# Sheet_1_2022-03-27.net
KiCad netlist of a schematic drawn in Altium Designer
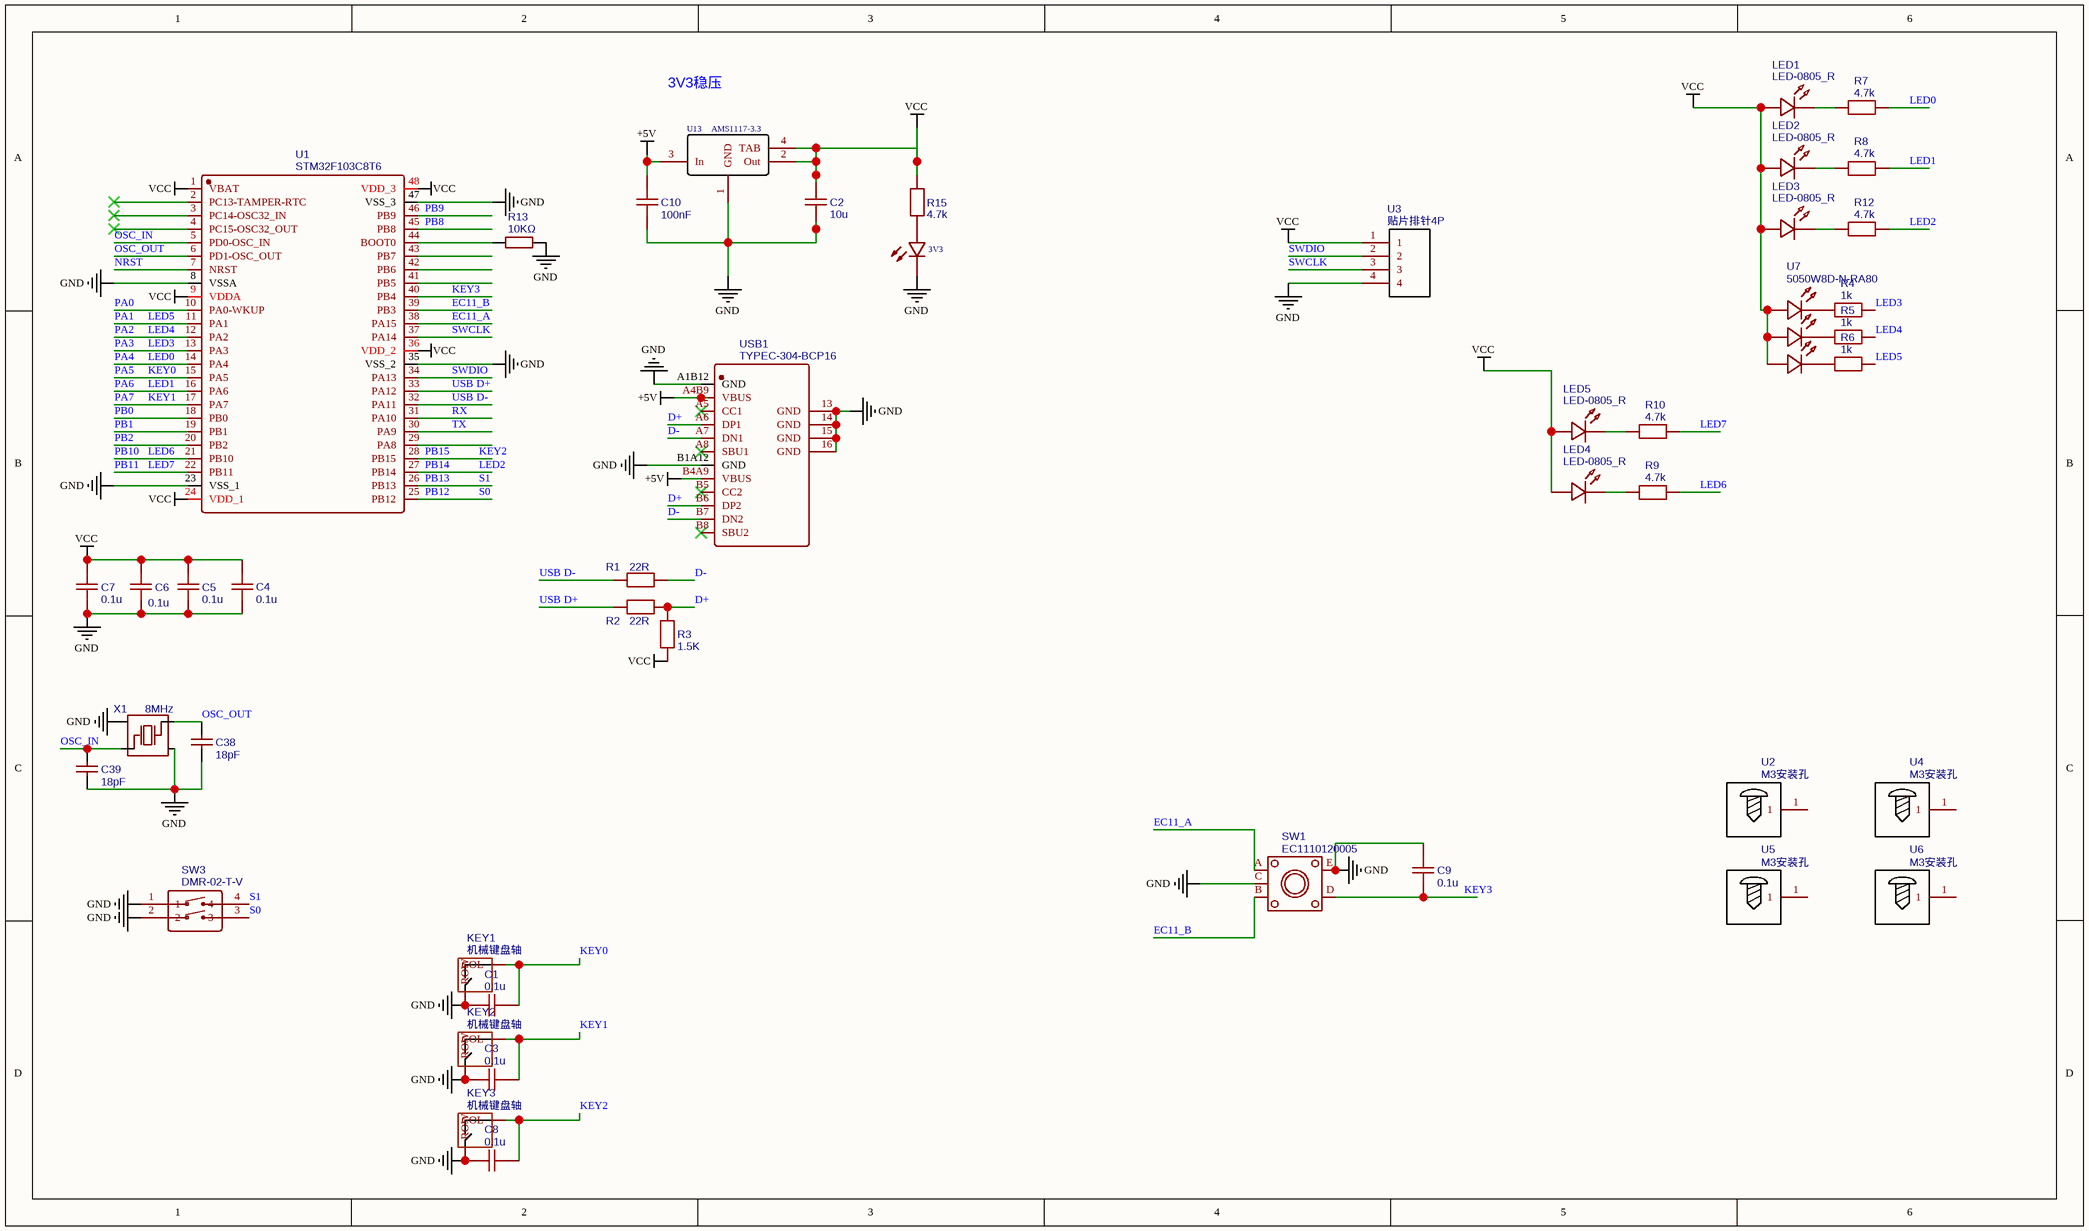
[diagram p0: Sheet_1_2022-03-27.schdoc]

(export (version "E")
  (design (tool "Eeschema 10.0.6"))
  (components
    (comp (ref "3V3")
      (value "17-21/BHC-XL2M2TY/3T")
      (fields (field (name "BOM_SUPPLIER PART") "C72035"))
      (libsource (lib "altium-import") (part "root_1_17-21/BHC-XL2M2TY/3T_"))
    )
    (comp (ref "C1")
      (value "0.1u")
      (fields (field (name "CONTRIBUTOR") "LCEDA_Lib"))
      (libsource (lib "altium-import") (part "root_2_0.1u_"))
    )
    (comp (ref "C2")
      (value "10u")
      (fields (field (name "CONTRIBUTOR") "LCEDA_Lib"))
      (libsource (lib "altium-import") (part "root_1_10u_"))
    )
    (comp (ref "C3")
      (value "0.1u")
      (fields (field (name "CONTRIBUTOR") "LCEDA_Lib"))
      (libsource (lib "altium-import") (part "root_0_0.1u_"))
    )
    (comp (ref "C4")
      (value "0.1u")
      (fields (field (name "CONTRIBUTOR") "LCEDA_Lib"))
      (libsource (lib "altium-import") (part "root_1_0.1u_"))
    )
    (comp (ref "C5")
      (value "0.1u")
      (fields (field (name "CONTRIBUTOR") "LCEDA_Lib"))
      (libsource (lib "altium-import") (part "root_1_0.1u_"))
    )
    (comp (ref "C6")
      (value "0.1u")
      (fields (field (name "CONTRIBUTOR") "LCEDA_Lib"))
      (libsource (lib "altium-import") (part "root_1_0.1u_"))
    )
    (comp (ref "C7")
      (value "0.1u")
      (fields (field (name "CONTRIBUTOR") "LCEDA_Lib"))
      (libsource (lib "altium-import") (part "root_1_0.1u_"))
    )
    (comp (ref "C8")
      (value "0.1u")
      (fields (field (name "CONTRIBUTOR") "LCEDA_Lib"))
      (libsource (lib "altium-import") (part "root_0_0.1u_"))
    )
    (comp (ref "C9")
      (value "0.1u")
      (fields (field (name "CONTRIBUTOR") "LCEDA_Lib"))
      (libsource (lib "altium-import") (part "root_3_0.1u_"))
    )
    (comp (ref "C10")
      (value "100nF")
      (fields (field (name "CONTRIBUTOR") "LCEDA_Lib"))
      (libsource (lib "altium-import") (part "root_1_100nF_"))
    )
    (comp (ref "C38")
      (value "18pF")
      (fields
        (field (name "BOM_MANUFACTURER PART") "CL10C180JB8NNNC")
        (field (name "BOM_SUPPLIER PART") "C1647")
      )
      (libsource (lib "altium-import") (part "root_1_18pF_"))
    )
    (comp (ref "C39")
      (value "18pF")
      (fields
        (field (name "BOM_MANUFACTURER PART") "CL10C180JB8NNNC")
        (field (name "BOM_SUPPLIER PART") "C1647")
      )
      (libsource (lib "altium-import") (part "root_1_18pF_"))
    )
    (comp (ref "KEY1")
      (value "机械键盘轴")
      (fields (field (name "CONTRIBUTOR") "Ptisak"))
      (libsource (lib "altium-import") (part "root_2_机械键盘轴_"))
    )
    (comp (ref "KEY2")
      (value "机械键盘轴")
      (fields (field (name "CONTRIBUTOR") "Ptisak"))
      (libsource (lib "altium-import") (part "root_2_机械键盘轴_"))
    )
    (comp (ref "KEY3")
      (value "机械键盘轴")
      (fields (field (name "CONTRIBUTOR") "Ptisak"))
      (libsource (lib "altium-import") (part "root_2_机械键盘轴_"))
    )
    (comp (ref "LED1")
      (value "LED-0805_R")
      (fields
        (field (name "BOM_MANUFACTURER PART") "17-21SURC/S530-A3/TR8")
        (field (name "BOM_SUPPLIER PART") "C72037")
        (field (name "CONTRIBUTOR") "LCEDA_Lib")
      )
      (libsource (lib "altium-import") (part "root_0_LED-0805_R_"))
    )
    (comp (ref "LED2")
      (value "LED-0805_R")
      (fields
        (field (name "BOM_MANUFACTURER PART") "17-21SURC/S530-A3/TR8")
        (field (name "BOM_SUPPLIER PART") "C72037")
        (field (name "CONTRIBUTOR") "LCEDA_Lib")
      )
      (libsource (lib "altium-import") (part "root_0_LED-0805_R_"))
    )
    (comp (ref "LED3")
      (value "LED-0805_R")
      (fields
        (field (name "BOM_MANUFACTURER PART") "17-21SURC/S530-A3/TR8")
        (field (name "BOM_SUPPLIER PART") "C72037")
        (field (name "CONTRIBUTOR") "LCEDA_Lib")
      )
      (libsource (lib "altium-import") (part "root_0_LED-0805_R_"))
    )
    (comp (ref "LED4")
      (value "LED-0805_R")
      (fields
        (field (name "BOM_MANUFACTURER PART") "17-21SURC/S530-A3/TR8")
        (field (name "BOM_SUPPLIER PART") "C72037")
        (field (name "CONTRIBUTOR") "LCEDA_Lib")
      )
      (libsource (lib "altium-import") (part "root_0_LED-0805_R_"))
    )
    (comp (ref "LED5")
      (value "LED-0805_R")
      (fields
        (field (name "BOM_MANUFACTURER PART") "17-21SURC/S530-A3/TR8")
        (field (name "BOM_SUPPLIER PART") "C72037")
        (field (name "CONTRIBUTOR") "LCEDA_Lib")
      )
      (libsource (lib "altium-import") (part "root_0_LED-0805_R_"))
    )
    (comp (ref "R1")
      (value "22R")
      (fields (field (name "CONTRIBUTOR") "LCEDA_Lib"))
      (libsource (lib "altium-import") (part "root_0_22R_"))
    )
    (comp (ref "R2")
      (value "22R")
      (fields (field (name "CONTRIBUTOR") "LCEDA_Lib"))
      (libsource (lib "altium-import") (part "root_0_22R_"))
    )
    (comp (ref "R3")
      (value "1.5K")
      (fields (field (name "CONTRIBUTOR") "LCEDA_Lib"))
      (libsource (lib "altium-import") (part "root_1_1.5K_"))
    )
    (comp (ref "R4")
      (value "1k")
      (fields (field (name "CONTRIBUTOR") "LCEDA_Lib"))
      (libsource (lib "altium-import") (part "root_0_1k_"))
    )
    (comp (ref "R5")
      (value "1k")
      (fields (field (name "CONTRIBUTOR") "LCEDA_Lib"))
      (libsource (lib "altium-import") (part "root_0_1k_"))
    )
    (comp (ref "R6")
      (value "1k")
      (fields (field (name "CONTRIBUTOR") "LCEDA_Lib"))
      (libsource (lib "altium-import") (part "root_0_1k_"))
    )
    (comp (ref "R7")
      (value "4.7k")
      (fields (field (name "CONTRIBUTOR") "LCEDA_Lib"))
      (libsource (lib "altium-import") (part "root_0_4.7k_"))
    )
    (comp (ref "R8")
      (value "4.7k")
      (fields (field (name "CONTRIBUTOR") "LCEDA_Lib"))
      (libsource (lib "altium-import") (part "root_0_4.7k_"))
    )
    (comp (ref "R9")
      (value "4.7k")
      (fields (field (name "CONTRIBUTOR") "LCEDA_Lib"))
      (libsource (lib "altium-import") (part "root_0_4.7k_"))
    )
    (comp (ref "R10")
      (value "4.7k")
      (fields (field (name "CONTRIBUTOR") "LCEDA_Lib"))
      (libsource (lib "altium-import") (part "root_0_4.7k_"))
    )
    (comp (ref "R12")
      (value "4.7k")
      (fields (field (name "CONTRIBUTOR") "LCEDA_Lib"))
      (libsource (lib "altium-import") (part "root_0_4.7k_"))
    )
    (comp (ref "R13")
      (value "10KΩ")
      (fields
        (field (name "BOM_MANUFACTURER PART") "0603WAF1002T5E")
        (field (name "BOM_SUPPLIER PART") "C25804")
      )
      (libsource (lib "altium-import") (part "root_2_10KΩ_"))
    )
    (comp (ref "R15")
      (value "4.7k")
      (fields (field (name "CONTRIBUTOR") "LCEDA_Lib"))
      (libsource (lib "altium-import") (part "root_1_4.7k_"))
    )
    (comp (ref "SW1")
      (value "EC1110120005")
      (fields (field (name "BOM_SUPPLIER PART") "C470788") (field (name "CONTRIBUTOR") "LCSC"))
      (libsource (lib "altium-import") (part "root_3_EC1110120005_"))
    )
    (comp (ref "SW3")
      (value "DMR-02-T-V")
      (fields (field (name "BOM_SUPPLIER PART") "C139554") (field (name "CONTRIBUTOR") "LCSC"))
      (libsource (lib "altium-import") (part "root_0_DMR-02-T-V_"))
    )
    (comp (ref "U1")
      (value "STM32F103C8T6")
      (fields (field (name "BOM_SUPPLIER PART") "C8734"))
      (libsource (lib "altium-import") (part "root_0_STM32F103C8T6_"))
    )
    (comp (ref "U2")
      (value "M3安装孔")
      (fields (field (name "CONTRIBUTOR") "Ptisak"))
      (libsource (lib "altium-import") (part "root_0_M3安装孔_"))
    )
    (comp (ref "U3")
      (value "贴片排针4P")
      (fields (field (name "CONTRIBUTOR") "Ptisak"))
      (libsource (lib "altium-import") (part "root_0_贴片排针4P_"))
    )
    (comp (ref "U4")
      (value "M3安装孔")
      (fields (field (name "CONTRIBUTOR") "Ptisak"))
      (libsource (lib "altium-import") (part "root_0_M3安装孔_"))
    )
    (comp (ref "U5")
      (value "M3安装孔")
      (fields (field (name "CONTRIBUTOR") "Ptisak"))
      (libsource (lib "altium-import") (part "root_0_M3安装孔_"))
    )
    (comp (ref "U6")
      (value "M3安装孔")
      (fields (field (name "CONTRIBUTOR") "Ptisak"))
      (libsource (lib "altium-import") (part "root_0_M3安装孔_"))
    )
    (comp (ref "U7")
      (value "5050W8D-N-RA80")
      (fields
        (field (name "BOM_SUPPLIER PART") "C2842550")
        (field (name "BOM_MANUFACTURER PART") "5050W8D-N-Ra80")
        (field (name "CONTRIBUTOR") "LCSC")
      )
      (libsource (lib "altium-import") (part "root_0_5050W8D-N-RA80_"))
    )
    (comp (ref "U13")
      (value "AMS1117-3.3")
      (fields (field (name "BOM_SUPPLIER PART") "C6187"))
      (libsource (lib "altium-import") (part "root_0_AMS1117-3.3_"))
    )
    (comp (ref "USB1")
      (value "TYPEC-304-BCP16")
      (fields (field (name "BOM_SUPPLIER PART") "C720629") (field (name "CONTRIBUTOR") "LCSC"))
      (libsource (lib "altium-import") (part "root_0_TYPEC-304-BCP16_"))
    )
    (comp (ref "X1")
      (value "8MHz")
      (fields
        (field (name "BOM_SUPPLIER PART") "C400090")
        (field (name "BOM_MANUFACTURER PART") "TAXM8M4RDBCCT2T")
        (field (name "CONTRIBUTOR") "LCSC")
      )
      (libsource (lib "altium-import") (part "root_0_8MHz_"))
    )
  )
  (nets
    (net (code "1") (name "+5V") (class "Default")
      (node (ref "C10") (pin "2") (pinfunction "2_2") (pintype "passive"))
      (node (ref "U13") (pin "3") (pinfunction "In_3") (pintype "passive"))
      (node (ref "USB1") (pin "A4B9") (pinfunction "VBUS_A4B9") (pintype "passive"))
      (node (ref "USB1") (pin "B4A9") (pinfunction "VBUS_B4A9") (pintype "passive"))
    )
    (net (code "2") (name "/D+") (class "Default")
      (node (ref "R2") (pin "2") (pinfunction "2_2") (pintype "passive"))
      (node (ref "R3") (pin "2") (pinfunction "2_2") (pintype "passive"))
      (node (ref "USB1") (pin "A6") (pinfunction "DP1_A6") (pintype "passive"))
      (node (ref "USB1") (pin "B6") (pinfunction "DP2_B6") (pintype "passive"))
    )
    (net (code "3") (name "/D-") (class "Default")
      (node (ref "R1") (pin "2") (pinfunction "2_2") (pintype "passive"))
      (node (ref "USB1") (pin "A7") (pinfunction "DN1_A7") (pintype "passive"))
      (node (ref "USB1") (pin "B7") (pinfunction "DN2_B7") (pintype "passive"))
    )
    (net (code "4") (name "/EC11_A") (class "Default")
      (node (ref "SW1") (pin "A") (pinfunction "A_A") (pintype "passive"))
      (node (ref "U1") (pin "38") (pinfunction "PA15_38") (pintype "passive"))
    )
    (net (code "5") (name "/EC11_B") (class "Default")
      (node (ref "SW1") (pin "B") (pinfunction "B_B") (pintype "passive"))
      (node (ref "U1") (pin "39") (pinfunction "PB3_39") (pintype "passive"))
    )
    (net (code "6") (name "/KEY0") (class "Default")
      (node (ref "C1") (pin "1") (pinfunction "1_1") (pintype "passive"))
      (node (ref "KEY1") (pin "COL") (pinfunction "COL_COL") (pintype "passive"))
      (node (ref "U1") (pin "15") (pinfunction "PA5_15") (pintype "passive"))
    )
    (net (code "7") (name "/KEY1") (class "Default")
      (node (ref "C3") (pin "2") (pinfunction "2_2") (pintype "passive"))
      (node (ref "KEY2") (pin "COL") (pinfunction "COL_COL") (pintype "passive"))
      (node (ref "U1") (pin "17") (pinfunction "PA7_17") (pintype "passive"))
    )
    (net (code "8") (name "/KEY2") (class "Default")
      (node (ref "C8") (pin "2") (pinfunction "2_2") (pintype "passive"))
      (node (ref "KEY3") (pin "COL") (pinfunction "COL_COL") (pintype "passive"))
      (node (ref "U1") (pin "28") (pinfunction "PB15_28") (pintype "passive"))
    )
    (net (code "9") (name "/KEY3") (class "Default")
      (node (ref "C9") (pin "2") (pinfunction "2_2") (pintype "passive"))
      (node (ref "SW1") (pin "D") (pinfunction "D_D") (pintype "passive"))
      (node (ref "U1") (pin "40") (pinfunction "PB4_40") (pintype "passive"))
    )
    (net (code "10") (name "/LED0") (class "Default")
      (node (ref "R7") (pin "2") (pinfunction "2_2") (pintype "passive"))
      (node (ref "U1") (pin "14") (pinfunction "PA4_14") (pintype "passive"))
    )
    (net (code "11") (name "/LED1") (class "Default")
      (node (ref "R8") (pin "2") (pinfunction "2_2") (pintype "passive"))
      (node (ref "U1") (pin "16") (pinfunction "PA6_16") (pintype "passive"))
    )
    (net (code "12") (name "/LED2") (class "Default")
      (node (ref "R12") (pin "2") (pinfunction "2_2") (pintype "passive"))
      (node (ref "U1") (pin "27") (pinfunction "PB14_27") (pintype "passive"))
    )
    (net (code "13") (name "/LED3") (class "Default")
      (node (ref "R4") (pin "2") (pinfunction "2_2") (pintype "passive"))
      (node (ref "U1") (pin "13") (pinfunction "PA3_13") (pintype "passive"))
    )
    (net (code "14") (name "/LED4") (class "Default")
      (node (ref "R5") (pin "2") (pinfunction "2_2") (pintype "passive"))
      (node (ref "U1") (pin "12") (pinfunction "PA2_12") (pintype "passive"))
    )
    (net (code "15") (name "/LED5") (class "Default")
      (node (ref "R6") (pin "2") (pinfunction "2_2") (pintype "passive"))
      (node (ref "U1") (pin "11") (pinfunction "PA1_11") (pintype "passive"))
    )
    (net (code "16") (name "/LED6") (class "Default")
      (node (ref "R9") (pin "2") (pinfunction "2_2") (pintype "passive"))
      (node (ref "U1") (pin "21") (pinfunction "PB10_21") (pintype "passive"))
    )
    (net (code "17") (name "/LED7") (class "Default")
      (node (ref "R10") (pin "2") (pinfunction "2_2") (pintype "passive"))
      (node (ref "U1") (pin "22") (pinfunction "PB11_22") (pintype "passive"))
    )
    (net (code "18") (name "/NRST") (class "Default")
      (node (ref "U1") (pin "7") (pinfunction "NRST_7") (pintype "passive"))
    )
    (net (code "19") (name "/OSC_IN") (class "Default")
      (node (ref "C39") (pin "2") (pinfunction "2_2") (pintype "passive"))
      (node (ref "U1") (pin "5") (pinfunction "PD0-OSC_IN_5") (pintype "passive"))
      (node (ref "X1") (pin "1") (pinfunction "1_1") (pintype "passive"))
    )
    (net (code "20") (name "/OSC_OUT") (class "Default")
      (node (ref "C38") (pin "2") (pinfunction "2_2") (pintype "passive"))
      (node (ref "U1") (pin "6") (pinfunction "PD1-OSC_OUT_6") (pintype "passive"))
      (node (ref "X1") (pin "3") (pinfunction "3_3") (pintype "passive"))
    )
    (net (code "21") (name "/PA0") (class "Default")
      (node (ref "U1") (pin "10") (pinfunction "PA0-WKUP_10") (pintype "passive"))
    )
    (net (code "22") (name "/PB0") (class "Default")
      (node (ref "U1") (pin "18") (pinfunction "PB0_18") (pintype "passive"))
    )
    (net (code "23") (name "/PB1") (class "Default")
      (node (ref "U1") (pin "19") (pinfunction "PB1_19") (pintype "passive"))
    )
    (net (code "24") (name "/PB2") (class "Default")
      (node (ref "U1") (pin "20") (pinfunction "PB2_20") (pintype "passive"))
    )
    (net (code "25") (name "/PB8") (class "Default")
      (node (ref "U1") (pin "45") (pinfunction "PB8_45") (pintype "passive"))
    )
    (net (code "26") (name "/PB9") (class "Default")
      (node (ref "U1") (pin "46") (pinfunction "PB9_46") (pintype "passive"))
    )
    (net (code "27") (name "/PB12") (class "Default")
      (node (ref "SW3") (pin "3") (pinfunction "3_3") (pintype "passive"))
      (node (ref "U1") (pin "25") (pinfunction "PB12_25") (pintype "passive"))
    )
    (net (code "28") (name "/PB13") (class "Default")
      (node (ref "SW3") (pin "4") (pinfunction "4_4") (pintype "passive"))
      (node (ref "U1") (pin "26") (pinfunction "PB13_26") (pintype "passive"))
    )
    (net (code "29") (name "/RX") (class "Default")
      (node (ref "U1") (pin "31") (pinfunction "PA10_31") (pintype "passive"))
    )
    (net (code "30") (name "/SWCLK") (class "Default")
      (node (ref "U1") (pin "37") (pinfunction "PA14_37") (pintype "passive"))
      (node (ref "U3") (pin "3") (pinfunction "3_3") (pintype "passive"))
    )
    (net (code "31") (name "/SWDIO") (class "Default")
      (node (ref "U1") (pin "34") (pinfunction "PA13_34") (pintype "passive"))
      (node (ref "U3") (pin "2") (pinfunction "2_2") (pintype "passive"))
    )
    (net (code "32") (name "/TX") (class "Default")
      (node (ref "U1") (pin "30") (pinfunction "PA9_30") (pintype "passive"))
    )
    (net (code "33") (name "/USB D+") (class "Default")
      (node (ref "R2") (pin "1") (pinfunction "1_1") (pintype "passive"))
      (node (ref "U1") (pin "33") (pinfunction "PA12_33") (pintype "passive"))
    )
    (net (code "34") (name "/USB D-") (class "Default")
      (node (ref "R1") (pin "1") (pinfunction "1_1") (pintype "passive"))
      (node (ref "U1") (pin "32") (pinfunction "PA11_32") (pintype "passive"))
    )
    (net (code "35") (name "GND") (class "Default")
      (node (ref "3V3") (pin "1") (pinfunction "-_1") (pintype "passive"))
      (node (ref "C1") (pin "2") (pinfunction "2_2") (pintype "passive"))
      (node (ref "C10") (pin "1") (pinfunction "1_1") (pintype "passive"))
      (node (ref "C2") (pin "1") (pinfunction "1_1") (pintype "passive"))
      (node (ref "C3") (pin "1") (pinfunction "1_1") (pintype "passive"))
      (node (ref "C38") (pin "1") (pinfunction "1_1") (pintype "passive"))
      (node (ref "C39") (pin "1") (pinfunction "1_1") (pintype "passive"))
      (node (ref "C4") (pin "1") (pinfunction "1_1") (pintype "passive"))
      (node (ref "C5") (pin "1") (pinfunction "1_1") (pintype "passive"))
      (node (ref "C6") (pin "1") (pinfunction "1_1") (pintype "passive"))
      (node (ref "C7") (pin "1") (pinfunction "1_1") (pintype "passive"))
      (node (ref "C8") (pin "1") (pinfunction "1_1") (pintype "passive"))
      (node (ref "C9") (pin "1") (pinfunction "1_1") (pintype "passive"))
      (node (ref "KEY1") (pin "ROW") (pinfunction "ROW_ROW") (pintype "passive"))
      (node (ref "KEY2") (pin "ROW") (pinfunction "ROW_ROW") (pintype "passive"))
      (node (ref "KEY3") (pin "ROW") (pinfunction "ROW_ROW") (pintype "passive"))
      (node (ref "R13") (pin "1") (pinfunction "1_1") (pintype "passive"))
      (node (ref "SW1") (pin "C") (pinfunction "C_C") (pintype "passive"))
      (node (ref "SW1") (pin "E") (pinfunction "E_E") (pintype "passive"))
      (node (ref "SW3") (pin "1") (pinfunction "1_1") (pintype "passive"))
      (node (ref "SW3") (pin "2") (pinfunction "2_2") (pintype "passive"))
      (node (ref "U1") (pin "23") (pinfunction "VSS_1_23") (pintype "passive"))
      (node (ref "U1") (pin "35") (pinfunction "VSS_2_35") (pintype "passive"))
      (node (ref "U1") (pin "47") (pinfunction "VSS_3_47") (pintype "passive"))
      (node (ref "U1") (pin "8") (pinfunction "VSSA_8") (pintype "passive"))
      (node (ref "U13") (pin "1") (pinfunction "GND_1") (pintype "passive"))
      (node (ref "U3") (pin "4") (pinfunction "4_4") (pintype "passive"))
      (node (ref "USB1") (pin "13") (pinfunction "GND_13") (pintype "passive"))
      (node (ref "USB1") (pin "14") (pinfunction "GND_14") (pintype "passive"))
      (node (ref "USB1") (pin "15") (pinfunction "GND_15") (pintype "passive"))
      (node (ref "USB1") (pin "16") (pinfunction "GND_16") (pintype "passive"))
      (node (ref "USB1") (pin "A1B12") (pinfunction "GND_A1B12") (pintype "passive"))
      (node (ref "USB1") (pin "B1A12") (pinfunction "GND_B1A12") (pintype "passive"))
      (node (ref "X1") (pin "2") (pinfunction "2_2") (pintype "passive"))
      (node (ref "X1") (pin "4") (pinfunction "4_4") (pintype "passive"))
    )
    (net (code "36") (name "Net-(3V3-+)") (class "Default")
      (node (ref "3V3") (pin "2") (pinfunction "+_2") (pintype "passive"))
      (node (ref "R15") (pin "1") (pinfunction "1_1") (pintype "passive"))
    )
    (net (code "37") (name "Net-(LED1-Pad2)") (class "Default")
      (node (ref "LED1") (pin "2") (pinfunction "2_2") (pintype "passive"))
      (node (ref "R7") (pin "1") (pinfunction "1_1") (pintype "passive"))
    )
    (net (code "38") (name "Net-(LED2-Pad2)") (class "Default")
      (node (ref "LED2") (pin "2") (pinfunction "2_2") (pintype "passive"))
      (node (ref "R8") (pin "1") (pinfunction "1_1") (pintype "passive"))
    )
    (net (code "39") (name "Net-(LED3-Pad2)") (class "Default")
      (node (ref "LED3") (pin "2") (pinfunction "2_2") (pintype "passive"))
      (node (ref "R12") (pin "1") (pinfunction "1_1") (pintype "passive"))
    )
    (net (code "40") (name "Net-(LED4-Pad2)") (class "Default")
      (node (ref "LED4") (pin "2") (pinfunction "2_2") (pintype "passive"))
      (node (ref "R9") (pin "1") (pinfunction "1_1") (pintype "passive"))
    )
    (net (code "41") (name "Net-(LED5-Pad2)") (class "Default")
      (node (ref "LED5") (pin "2") (pinfunction "2_2") (pintype "passive"))
      (node (ref "R10") (pin "1") (pinfunction "1_1") (pintype "passive"))
    )
    (net (code "42") (name "Net-(R4-Pad1)") (class "Default")
      (node (ref "R4") (pin "1") (pinfunction "1_1") (pintype "passive"))
      (node (ref "U7") (pin "3") (pinfunction "K_3") (pintype "passive"))
    )
    (net (code "43") (name "Net-(R5-Pad1)") (class "Default")
      (node (ref "R5") (pin "1") (pinfunction "1_1") (pintype "passive"))
      (node (ref "U7") (pin "2") (pinfunction "K_2") (pintype "passive"))
    )
    (net (code "44") (name "Net-(R6-Pad1)") (class "Default")
      (node (ref "R6") (pin "1") (pinfunction "1_1") (pintype "passive"))
      (node (ref "U7") (pin "1") (pinfunction "K_1") (pintype "passive"))
    )
    (net (code "45") (name "Net-(U1-BOOT0)") (class "Default")
      (node (ref "R13") (pin "2") (pinfunction "2_2") (pintype "passive"))
      (node (ref "U1") (pin "44") (pinfunction "BOOT0_44") (pintype "passive"))
    )
    (net (code "46") (name "VCC") (class "Default")
      (node (ref "C2") (pin "2") (pinfunction "2_2") (pintype "passive"))
      (node (ref "C4") (pin "2") (pinfunction "2_2") (pintype "passive"))
      (node (ref "C5") (pin "2") (pinfunction "2_2") (pintype "passive"))
      (node (ref "C6") (pin "2") (pinfunction "2_2") (pintype "passive"))
      (node (ref "C7") (pin "2") (pinfunction "2_2") (pintype "passive"))
      (node (ref "LED1") (pin "1") (pinfunction "1_1") (pintype "passive"))
      (node (ref "LED2") (pin "1") (pinfunction "1_1") (pintype "passive"))
      (node (ref "LED3") (pin "1") (pinfunction "1_1") (pintype "passive"))
      (node (ref "LED4") (pin "1") (pinfunction "1_1") (pintype "passive"))
      (node (ref "LED5") (pin "1") (pinfunction "1_1") (pintype "passive"))
      (node (ref "R15") (pin "2") (pinfunction "2_2") (pintype "passive"))
      (node (ref "R3") (pin "1") (pinfunction "1_1") (pintype "passive"))
      (node (ref "U1") (pin "1") (pinfunction "VBAT_1") (pintype "passive"))
      (node (ref "U1") (pin "24") (pinfunction "VDD_1_24") (pintype "passive"))
      (node (ref "U1") (pin "36") (pinfunction "VDD_2_36") (pintype "passive"))
      (node (ref "U1") (pin "48") (pinfunction "VDD_3_48") (pintype "passive"))
      (node (ref "U1") (pin "9") (pinfunction "VDDA_9") (pintype "passive"))
      (node (ref "U13") (pin "2") (pinfunction "Out_2") (pintype "passive"))
      (node (ref "U13") (pin "4") (pinfunction "TAB_4") (pintype "passive"))
      (node (ref "U3") (pin "1") (pinfunction "1_1") (pintype "passive"))
      (node (ref "U7") (pin "4") (pinfunction "A_4") (pintype "passive"))
      (node (ref "U7") (pin "5") (pinfunction "A_5") (pintype "passive"))
      (node (ref "U7") (pin "6") (pinfunction "A_6") (pintype "passive"))
    )
    (net (code "47") (name "unconnected-(U1-PA8-Pad29)") (class "Default")
      (node (ref "U1") (pin "29") (pinfunction "PA8_29") (pintype "passive"))
    )
    (net (code "48") (name "unconnected-(U1-PB5-Pad41)") (class "Default")
      (node (ref "U1") (pin "41") (pinfunction "PB5_41") (pintype "passive"))
    )
    (net (code "49") (name "unconnected-(U1-PB6-Pad42)") (class "Default")
      (node (ref "U1") (pin "42") (pinfunction "PB6_42") (pintype "passive"))
    )
    (net (code "50") (name "unconnected-(U1-PB7-Pad43)") (class "Default")
      (node (ref "U1") (pin "43") (pinfunction "PB7_43") (pintype "passive"))
    )
    (net (code "51") (name "unconnected-(U1-PC13-TAMPER-RTC-Pad2)") (class "Default")
      (node (ref "U1") (pin "2") (pinfunction "PC13-TAMPER-RTC_2") (pintype "passive+no_connect"))
    )
    (net (code "52") (name "unconnected-(U1-PC14-OSC32_IN-Pad3)") (class "Default")
      (node (ref "U1") (pin "3") (pinfunction "PC14-OSC32_IN_3") (pintype "passive+no_connect"))
    )
    (net (code "53") (name "unconnected-(U1-PC15-OSC32_OUT-Pad4)") (class "Default")
      (node (ref "U1") (pin "4") (pinfunction "PC15-OSC32_OUT_4") (pintype "passive+no_connect"))
    )
    (net (code "54") (name "unconnected-(U2-Pad1)") (class "Default")
      (node (ref "U2") (pin "1") (pinfunction "1_1") (pintype "passive"))
    )
    (net (code "55") (name "unconnected-(U4-Pad1)") (class "Default")
      (node (ref "U4") (pin "1") (pinfunction "1_1") (pintype "passive"))
    )
    (net (code "56") (name "unconnected-(U5-Pad1)") (class "Default")
      (node (ref "U5") (pin "1") (pinfunction "1_1") (pintype "passive"))
    )
    (net (code "57") (name "unconnected-(U6-Pad1)") (class "Default")
      (node (ref "U6") (pin "1") (pinfunction "1_1") (pintype "passive"))
    )
    (net (code "58") (name "unconnected-(USB1-CC1-PadA5)") (class "Default")
      (node (ref "USB1") (pin "A5") (pinfunction "CC1_A5") (pintype "passive+no_connect"))
    )
    (net (code "59") (name "unconnected-(USB1-CC2-PadB5)") (class "Default")
      (node (ref "USB1") (pin "B5") (pinfunction "CC2_B5") (pintype "passive+no_connect"))
    )
    (net (code "60") (name "unconnected-(USB1-SBU1-PadA8)") (class "Default")
      (node (ref "USB1") (pin "A8") (pinfunction "SBU1_A8") (pintype "passive+no_connect"))
    )
    (net (code "61") (name "unconnected-(USB1-SBU2-PadB8)") (class "Default")
      (node (ref "USB1") (pin "B8") (pinfunction "SBU2_B8") (pintype "passive+no_connect"))
    )
  )
)
